# Ethernet_0_V1_01.net
KiCad netlist of a schematic drawn in Altium Designer
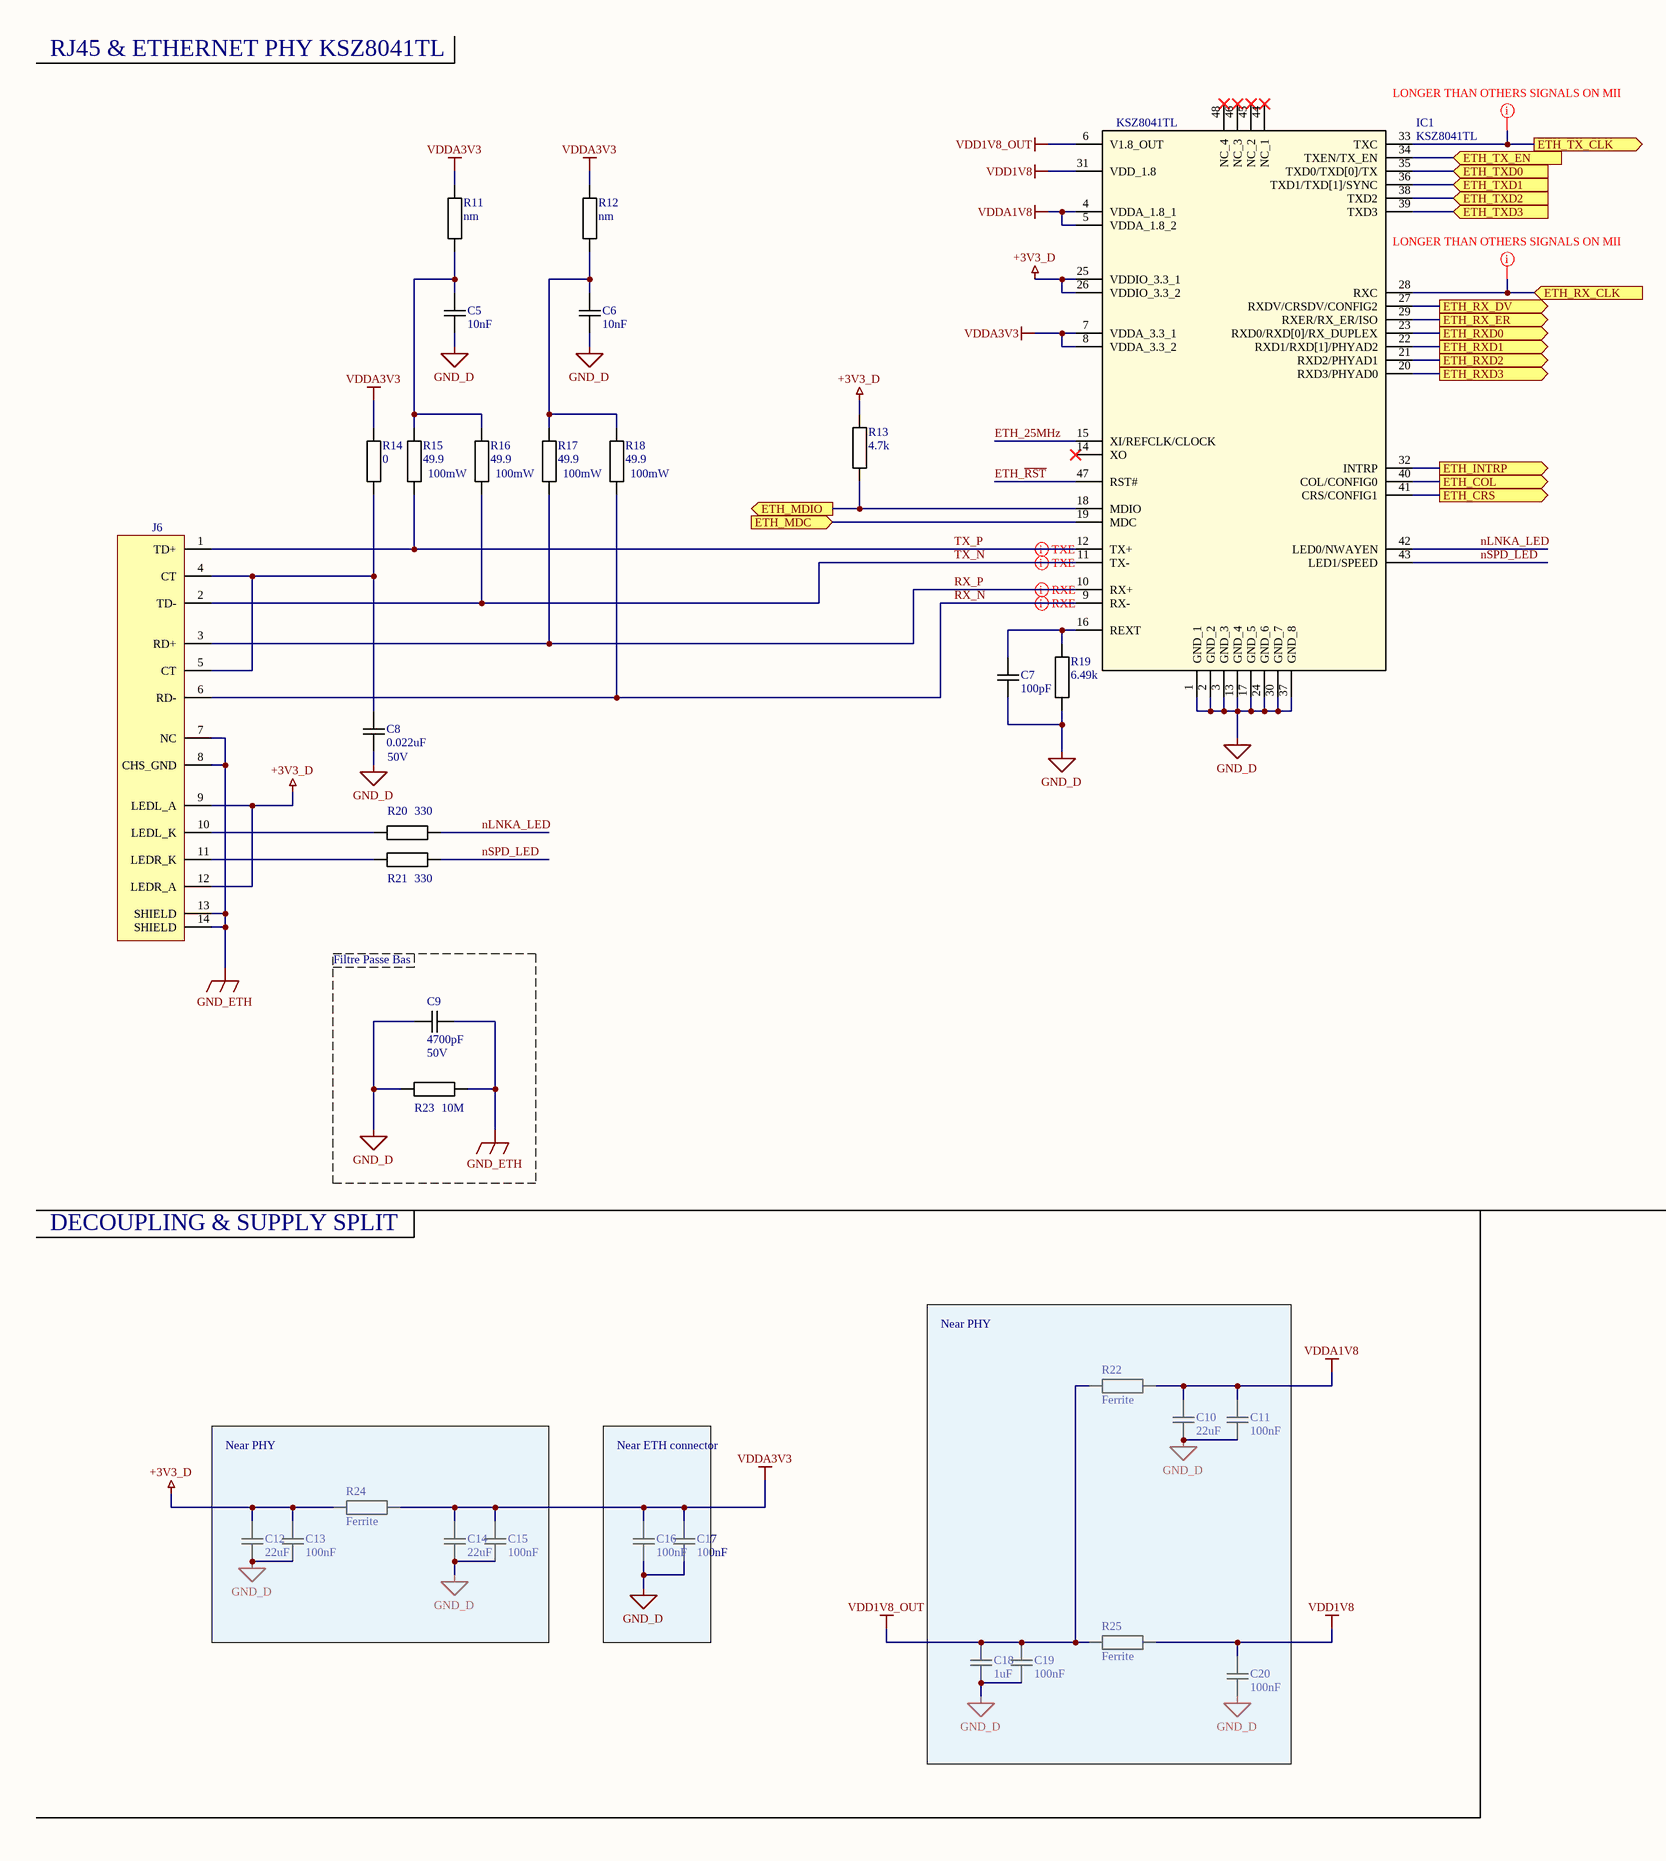
[diagram p0: Ethernet_0_V1_01.SchDoc, left]
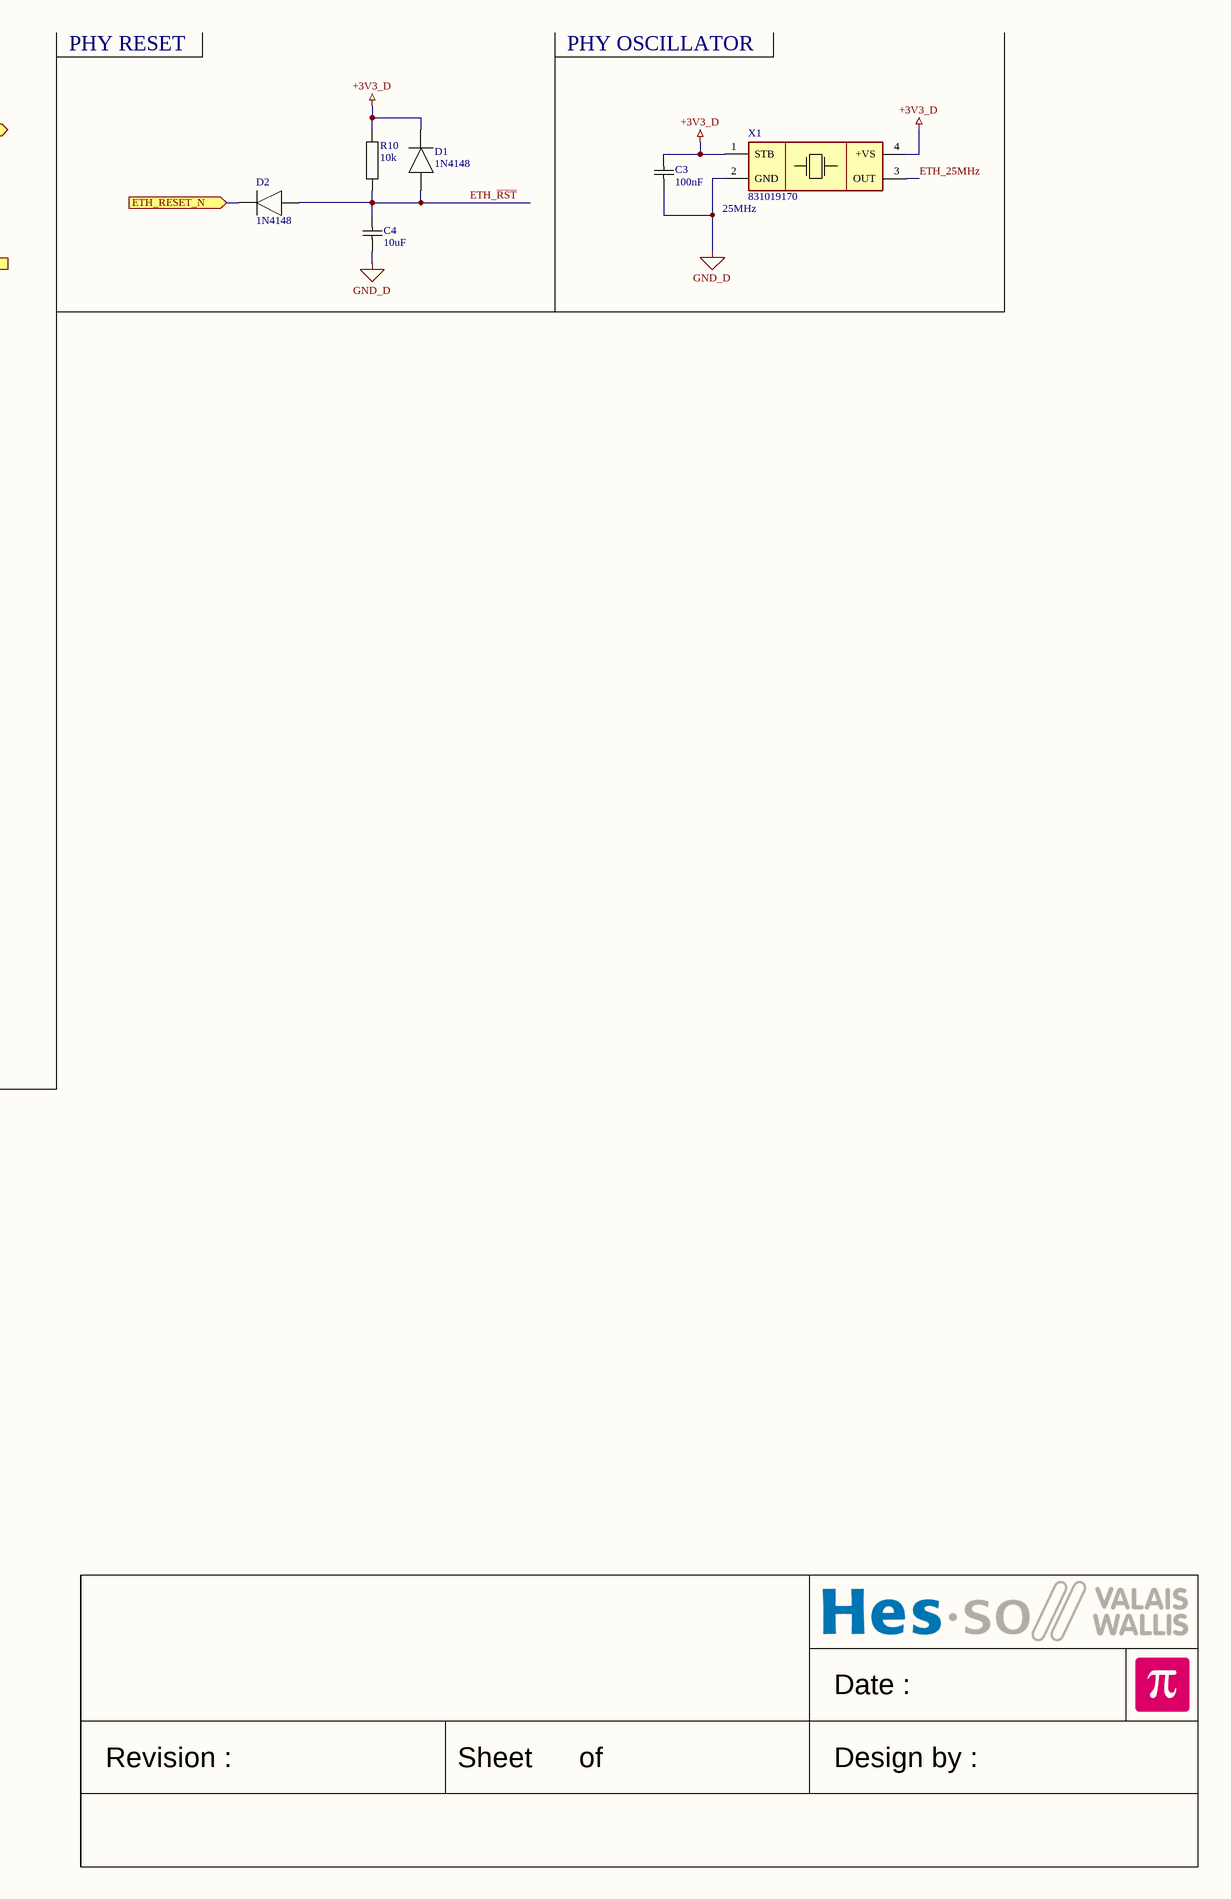
[diagram p1: Ethernet_0_V1_01.SchDoc, right]

(export (version "E")
  (design (tool "Eeschema 10.0.6"))
  (components
    (comp (ref "C3")
      (value "100nF")
      (footprint "CAPACITOR 1608 REFLOW")
      (description "Capacitor X7R 10% 50V 1608(0603)")
      (libsource (lib "Capacitor") (part "Capacitor"))
    )
    (comp (ref "C4")
      (value "10uF")
      (footprint "CAPACITOR 2012 REFLOW")
      (description "Capacitor X7R 10% 50V 1608(0603)")
      (libsource (lib "Capacitor") (part "Capacitor"))
    )
    (comp (ref "C5")
      (value "10nF")
      (footprint "CAPACITOR 1608 REFLOW")
      (description "Capacitor X7R 10% 50V 1608(0603)")
      (libsource (lib "Capacitor") (part "Capacitor"))
    )
    (comp (ref "C6")
      (value "10nF")
      (footprint "CAPACITOR 1608 REFLOW")
      (description "Capacitor X7R 10% 50V 1608(0603)")
      (libsource (lib "Capacitor") (part "Capacitor"))
    )
    (comp (ref "C7")
      (value "100pF")
      (footprint "CAPACITOR 1608 REFLOW")
      (description "Capacitor X7R 10% 50V 1608(0603)")
      (libsource (lib "Capacitor") (part "Capacitor"))
    )
    (comp (ref "C8")
      (value "0.022uF")
      (footprint "CAPACITOR 1608 REFLOW")
      (description "Capacitor")
      (fields (field (name "V") "50V"))
      (libsource (lib "Capacitor") (part "Capacitor"))
    )
    (comp (ref "C9")
      (value "4700pF")
      (footprint "CAPACITOR 1608 REFLOW")
      (description "Capacitor")
      (fields (field (name "U") "50V"))
      (libsource (lib "Capacitor") (part "Capacitor"))
    )
    (comp (ref "C10")
      (value "22uF")
      (footprint "CAPACITOR 2012 REFLOW")
      (description "Capacitor X7R 10% 50V 1608(0603)")
      (libsource (lib "Capacitor") (part "Capacitor"))
    )
    (comp (ref "C11")
      (value "100nF")
      (footprint "CAPACITOR 1608 REFLOW")
      (description "Capacitor X7R 10% 50V 1608(0603)")
      (libsource (lib "Capacitor") (part "Capacitor"))
    )
    (comp (ref "C12")
      (value "22uF")
      (footprint "CAPACITOR 2012 REFLOW")
      (description "Capacitor X7R 10% 50V 1608(0603)")
      (libsource (lib "Capacitor") (part "Capacitor"))
    )
    (comp (ref "C13")
      (value "100nF")
      (footprint "CAPACITOR 1608 REFLOW")
      (description "Capacitor X7R 10% 50V 1608(0603)")
      (libsource (lib "Capacitor") (part "Capacitor"))
    )
    (comp (ref "C14")
      (value "22uF")
      (footprint "CAPACITOR 2012 REFLOW")
      (description "Capacitor X7R 10% 50V 1608(0603)")
      (libsource (lib "Capacitor") (part "Capacitor"))
    )
    (comp (ref "C15")
      (value "100nF")
      (footprint "CAPACITOR 1608 REFLOW")
      (description "Capacitor X7R 10% 50V 1608(0603)")
      (libsource (lib "Capacitor") (part "Capacitor"))
    )
    (comp (ref "C16")
      (value "100nF")
      (footprint "CAPACITOR 1608 REFLOW")
      (description "Capacitor X7R 10% 50V 1608(0603)")
      (libsource (lib "Capacitor") (part "Capacitor"))
    )
    (comp (ref "C17")
      (value "100nF")
      (footprint "CAPACITOR 1608 REFLOW")
      (description "Capacitor X7R 10% 50V 1608(0603)")
      (libsource (lib "Capacitor") (part "Capacitor"))
    )
    (comp (ref "C18")
      (value "1uF")
      (footprint "CAPACITOR 2012 REFLOW")
      (description "Capacitor X7R 10% 50V 1608(0603)")
      (libsource (lib "Capacitor") (part "Capacitor"))
    )
    (comp (ref "C19")
      (value "100nF")
      (footprint "CAPACITOR 1608 REFLOW")
      (description "Capacitor X7R 10% 50V 1608(0603)")
      (libsource (lib "Capacitor") (part "Capacitor"))
    )
    (comp (ref "C20")
      (value "100nF")
      (footprint "CAPACITOR 1608 REFLOW")
      (description "Capacitor X7R 10% 50V 1608(0603)")
      (libsource (lib "Capacitor") (part "Capacitor"))
    )
    (comp (ref "D1")
      (value "1N4148")
      (footprint "DIODE SOD323 REFLOW")
      (description "Diode generic 2 leads")
      (libsource (lib "Diode") (part "DIODE"))
    )
    (comp (ref "D2")
      (value "1N4148")
      (footprint "DIODE SOD323 REFLOW")
      (description "Diode generic 2 leads")
      (libsource (lib "Diode") (part "DIODE"))
    )
    (comp (ref "IC1")
      (value "KSZ8041TL")
      (footprint "SamacSys:QFP50P900X900X105-48N")
      (description "Integrated Circuit")
      (fields
        (field (name "MANUFACTURER_PART_NUMBER") "KSZ8041TL")
        (field (name "MOUSER PART NUMBER") "998-KSZ8041TL")
      )
      (libsource (lib "SamacSys") (part "KSZ8041TL"))
    )
    (comp (ref "J6")
      (value "RJ45-PULSE-J0011D21BNL")
      (footprint "RJ45 PULSE J0011D21BNL")
      (description "Integrated connector modules 10/100 base-TX belMag with LEDs")
      (libsource (lib "Connector") (part "RJ45 PULSE J0011D21BNL"))
    )
    (comp (ref "R10")
      (value "10k")
      (footprint "RESISTOR 1608 REFLOW")
      (description "Resistor 1% 50V 100mW 1608(0603)")
      (libsource (lib "Resistor") (part "Resistor"))
    )
    (comp (ref "R11")
      (value "nm")
      (footprint "RESISTOR 1608 REFLOW")
      (description "Resistor")
      (libsource (lib "Resistor") (part "Resistor"))
    )
    (comp (ref "R12")
      (value "nm")
      (footprint "RESISTOR 1608 REFLOW")
      (description "Resistor")
      (libsource (lib "Resistor") (part "Resistor"))
    )
    (comp (ref "R13")
      (value "4.7k")
      (footprint "RESISTOR 1608 REFLOW")
      (description "Resistor 1% 50V 100mW 1608(0603)")
      (libsource (lib "Resistor") (part "Resistor"))
    )
    (comp (ref "R14")
      (value "0")
      (footprint "RESISTOR 1608 REFLOW")
      (description "Resistor")
      (libsource (lib "Resistor") (part "Resistor"))
    )
    (comp (ref "R15")
      (value "49.9")
      (footprint "RESISTOR 1608 REFLOW")
      (description "Resistor")
      (fields (field (name "W") "100mW"))
      (libsource (lib "Resistor") (part "Resistor"))
    )
    (comp (ref "R16")
      (value "49.9")
      (footprint "RESISTOR 1608 REFLOW")
      (description "Resistor")
      (fields (field (name "W") "100mW"))
      (libsource (lib "Resistor") (part "Resistor"))
    )
    (comp (ref "R17")
      (value "49.9")
      (footprint "RESISTOR 1608 REFLOW")
      (description "Resistor")
      (fields (field (name "W") "100mW"))
      (libsource (lib "Resistor") (part "Resistor"))
    )
    (comp (ref "R18")
      (value "49.9")
      (footprint "RESISTOR 1608 REFLOW")
      (description "Resistor")
      (fields (field (name "W") "100mW"))
      (libsource (lib "Resistor") (part "Resistor"))
    )
    (comp (ref "R19")
      (value "6.49k")
      (footprint "RESISTOR 1608 REFLOW")
      (description "Resistor 1% 50V 100mW 1608(0603)")
      (libsource (lib "Resistor") (part "Resistor"))
    )
    (comp (ref "R20")
      (value "330")
      (footprint "RESISTOR 1608 REFLOW")
      (description "Resistor")
      (libsource (lib "Resistor") (part "Resistor"))
    )
    (comp (ref "R21")
      (value "330")
      (footprint "RESISTOR 1608 REFLOW")
      (description "Resistor")
      (libsource (lib "Resistor") (part "Resistor"))
    )
    (comp (ref "R22")
      (value "Ferrite")
      (footprint "RESISTOR 1608 REFLOW")
      (description "Resistor 1% 50V 100mW 1608(0603)")
      (libsource (lib "Resistor") (part "Resistor"))
    )
    (comp (ref "R23")
      (value "10M")
      (footprint "RESISTOR 1608 REFLOW")
      (description "Resistor")
      (libsource (lib "Resistor") (part "Resistor"))
    )
    (comp (ref "R24")
      (value "Ferrite")
      (footprint "RESISTOR 1608 REFLOW")
      (description "Resistor 1% 50V 100mW 1608(0603)")
      (libsource (lib "Resistor") (part "Resistor"))
    )
    (comp (ref "R25")
      (value "Ferrite")
      (footprint "RESISTOR 1608 REFLOW")
      (description "Resistor 1% 50V 100mW 1608(0603)")
      (libsource (lib "Resistor") (part "Resistor"))
    )
    (comp (ref "X1")
      (value "831019170")
      (footprint "Oscillator C5.2x7.2 IQD LFSPXO")
      (description "Oscillator C5.2x7.2 IQD LFSPXO")
      (fields (field (name "FREQ") "25MHz"))
      (libsource (lib "Oscillator") (part "Oscillator C5.2x7.2 IQD LFSPXO"))
    )
  )
  (nets
    (net (code "1") (name "+3V3_D") (class "Default")
      (node (ref "C12") (pin "2") (pinfunction "2_2") (pintype "passive"))
      (node (ref "C13") (pin "2") (pinfunction "2_2") (pintype "passive"))
      (node (ref "C3") (pin "2") (pinfunction "2_2") (pintype "passive"))
      (node (ref "D1") (pin "1") (pinfunction "C_1") (pintype "passive"))
      (node (ref "IC1") (pin "25") (pinfunction "VDDIO_3.3_1_25") (pintype "passive"))
      (node (ref "IC1") (pin "26") (pinfunction "VDDIO_3.3_2_26") (pintype "passive"))
      (node (ref "J6") (pin "12") (pinfunction "LEDR_A_12") (pintype "passive"))
      (node (ref "J6") (pin "9") (pinfunction "LEDL_A_9") (pintype "passive"))
      (node (ref "R10") (pin "2") (pinfunction "2_2") (pintype "passive"))
      (node (ref "R13") (pin "2") (pinfunction "2_2") (pintype "passive"))
      (node (ref "R24") (pin "2") (pinfunction "2_2") (pintype "passive"))
      (node (ref "X1") (pin "1") (pinfunction "STB_1") (pintype "passive"))
      (node (ref "X1") (pin "4") (pinfunction "+VS_4") (pintype "passive"))
    )
    (net (code "2") (name "/ETH_25MHz") (class "Default")
      (node (ref "IC1") (pin "15") (pinfunction "XI/REFCLK/CLOCK_15") (pintype "passive"))
      (node (ref "X1") (pin "3") (pinfunction "OUT_3") (pintype "passive"))
    )
    (net (code "3") (name "/ETH_COL") (class "Default")
      (node (ref "IC1") (pin "40") (pinfunction "COL/CONFIG0_40") (pintype "passive"))
    )
    (net (code "4") (name "/ETH_CRS") (class "Default")
      (node (ref "IC1") (pin "41") (pinfunction "CRS/CONFIG1_41") (pintype "passive"))
    )
    (net (code "5") (name "/ETH_INTRP") (class "Default")
      (node (ref "IC1") (pin "32") (pinfunction "INTRP_32") (pintype "passive"))
    )
    (net (code "6") (name "/ETH_MDC") (class "Default")
      (node (ref "IC1") (pin "19") (pinfunction "MDC_19") (pintype "passive"))
    )
    (net (code "7") (name "/ETH_MDIO") (class "Default")
      (node (ref "IC1") (pin "18") (pinfunction "MDIO_18") (pintype "passive"))
      (node (ref "R13") (pin "1") (pinfunction "1_1") (pintype "passive"))
    )
    (net (code "8") (name "/ETH_RESET_N") (class "Default")
      (node (ref "D2") (pin "1") (pinfunction "C_1") (pintype "passive"))
    )
    (net (code "9") (name "/ETH_RXD0") (class "Default")
      (node (ref "IC1") (pin "23") (pinfunction "RXD0/RXD[0]/RX_DUPLEX_23") (pintype "passive"))
    )
    (net (code "10") (name "/ETH_RXD1") (class "Default")
      (node (ref "IC1") (pin "22") (pinfunction "RXD1/RXD[1]/PHYAD2_22") (pintype "passive"))
    )
    (net (code "11") (name "/ETH_RXD2") (class "Default")
      (node (ref "IC1") (pin "21") (pinfunction "RXD2/PHYAD1_21") (pintype "passive"))
    )
    (net (code "12") (name "/ETH_RXD3") (class "Default")
      (node (ref "IC1") (pin "20") (pinfunction "RXD3/PHYAD0_20") (pintype "passive"))
    )
    (net (code "13") (name "/ETH_RX_CLK") (class "Default")
      (node (ref "IC1") (pin "28") (pinfunction "RXC_28") (pintype "passive"))
    )
    (net (code "14") (name "/ETH_RX_DV") (class "Default")
      (node (ref "IC1") (pin "27") (pinfunction "RXDV/CRSDV/CONFIG2_27") (pintype "passive"))
    )
    (net (code "15") (name "/ETH_RX_ER") (class "Default")
      (node (ref "IC1") (pin "29") (pinfunction "RXER/RX_ER/ISO_29") (pintype "passive"))
    )
    (net (code "16") (name "/ETH_TXD0") (class "Default")
      (node (ref "IC1") (pin "35") (pinfunction "TXD0/TXD[0]/TX_35") (pintype "passive"))
    )
    (net (code "17") (name "/ETH_TXD1") (class "Default")
      (node (ref "IC1") (pin "36") (pinfunction "TXD1/TXD[1]/SYNC_36") (pintype "passive"))
    )
    (net (code "18") (name "/ETH_TXD2") (class "Default")
      (node (ref "IC1") (pin "38") (pinfunction "TXD2_38") (pintype "passive"))
    )
    (net (code "19") (name "/ETH_TXD3") (class "Default")
      (node (ref "IC1") (pin "39") (pinfunction "TXD3_39") (pintype "passive"))
    )
    (net (code "20") (name "/ETH_TX_CLK") (class "Default")
      (node (ref "IC1") (pin "33") (pinfunction "TXC_33") (pintype "passive"))
    )
    (net (code "21") (name "/ETH_TX_EN") (class "Default")
      (node (ref "IC1") (pin "34") (pinfunction "TXEN/TX_EN_34") (pintype "passive"))
    )
    (net (code "22") (name "/ETH_~{RST}") (class "Default")
      (node (ref "C4") (pin "2") (pinfunction "2_2") (pintype "passive"))
      (node (ref "D1") (pin "2") (pinfunction "A_2") (pintype "passive"))
      (node (ref "D2") (pin "2") (pinfunction "A_2") (pintype "passive"))
      (node (ref "IC1") (pin "47") (pinfunction "RST#_47") (pintype "passive"))
      (node (ref "R10") (pin "1") (pinfunction "1_1") (pintype "passive"))
    )
    (net (code "23") (name "/RX_N") (class "Default")
      (node (ref "IC1") (pin "9") (pinfunction "RX-_9") (pintype "passive"))
      (node (ref "J6") (pin "6") (pinfunction "RD-_6") (pintype "passive"))
      (node (ref "R18") (pin "1") (pinfunction "1_1") (pintype "passive"))
    )
    (net (code "24") (name "/RX_P") (class "Default")
      (node (ref "IC1") (pin "10") (pinfunction "RX+_10") (pintype "passive"))
      (node (ref "J6") (pin "3") (pinfunction "RD+_3") (pintype "passive"))
      (node (ref "R17") (pin "1") (pinfunction "1_1") (pintype "passive"))
    )
    (net (code "25") (name "/TX_N") (class "Default")
      (node (ref "IC1") (pin "11") (pinfunction "TX-_11") (pintype "passive"))
      (node (ref "J6") (pin "2") (pinfunction "TD-_2") (pintype "passive"))
      (node (ref "R16") (pin "1") (pinfunction "1_1") (pintype "passive"))
    )
    (net (code "26") (name "/TX_P") (class "Default")
      (node (ref "IC1") (pin "12") (pinfunction "TX+_12") (pintype "passive"))
      (node (ref "J6") (pin "1") (pinfunction "TD+_1") (pintype "passive"))
      (node (ref "R15") (pin "1") (pinfunction "1_1") (pintype "passive"))
    )
    (net (code "27") (name "/nLNKA_LED") (class "Default")
      (node (ref "IC1") (pin "42") (pinfunction "LED0/NWAYEN_42") (pintype "passive"))
      (node (ref "R20") (pin "1") (pinfunction "1_1") (pintype "passive"))
    )
    (net (code "28") (name "/nSPD_LED") (class "Default")
      (node (ref "IC1") (pin "43") (pinfunction "LED1/SPEED_43") (pintype "passive"))
      (node (ref "R21") (pin "1") (pinfunction "1_1") (pintype "passive"))
    )
    (net (code "29") (name "GND_D") (class "Default")
      (node (ref "C10") (pin "1") (pinfunction "1_1") (pintype "passive"))
      (node (ref "C11") (pin "1") (pinfunction "1_1") (pintype "passive"))
      (node (ref "C12") (pin "1") (pinfunction "1_1") (pintype "passive"))
      (node (ref "C13") (pin "1") (pinfunction "1_1") (pintype "passive"))
      (node (ref "C14") (pin "1") (pinfunction "1_1") (pintype "passive"))
      (node (ref "C15") (pin "1") (pinfunction "1_1") (pintype "passive"))
      (node (ref "C16") (pin "1") (pinfunction "1_1") (pintype "passive"))
      (node (ref "C17") (pin "1") (pinfunction "1_1") (pintype "passive"))
      (node (ref "C18") (pin "1") (pinfunction "1_1") (pintype "passive"))
      (node (ref "C19") (pin "1") (pinfunction "1_1") (pintype "passive"))
      (node (ref "C20") (pin "1") (pinfunction "1_1") (pintype "passive"))
      (node (ref "C3") (pin "1") (pinfunction "1_1") (pintype "passive"))
      (node (ref "C4") (pin "1") (pinfunction "1_1") (pintype "passive"))
      (node (ref "C5") (pin "1") (pinfunction "1_1") (pintype "passive"))
      (node (ref "C6") (pin "1") (pinfunction "1_1") (pintype "passive"))
      (node (ref "C7") (pin "1") (pinfunction "1_1") (pintype "passive"))
      (node (ref "C8") (pin "2") (pinfunction "2_2") (pintype "passive"))
      (node (ref "C9") (pin "1") (pinfunction "1_1") (pintype "passive"))
      (node (ref "IC1") (pin "1") (pinfunction "GND_1_1") (pintype "passive"))
      (node (ref "IC1") (pin "13") (pinfunction "GND_4_13") (pintype "passive"))
      (node (ref "IC1") (pin "17") (pinfunction "GND_5_17") (pintype "passive"))
      (node (ref "IC1") (pin "2") (pinfunction "GND_2_2") (pintype "passive"))
      (node (ref "IC1") (pin "24") (pinfunction "GND_6_24") (pintype "passive"))
      (node (ref "IC1") (pin "3") (pinfunction "GND_3_3") (pintype "passive"))
      (node (ref "IC1") (pin "30") (pinfunction "GND_7_30") (pintype "passive"))
      (node (ref "IC1") (pin "37") (pinfunction "GND_8_37") (pintype "passive"))
      (node (ref "R19") (pin "1") (pinfunction "1_1") (pintype "passive"))
      (node (ref "R23") (pin "2") (pinfunction "2_2") (pintype "passive"))
      (node (ref "X1") (pin "2") (pinfunction "GND_2") (pintype "passive"))
    )
    (net (code "30") (name "GND_ETH") (class "Default")
      (node (ref "C9") (pin "2") (pinfunction "2_2") (pintype "passive"))
      (node (ref "J6") (pin "13") (pinfunction "SHIELD_13") (pintype "passive"))
      (node (ref "J6") (pin "14") (pinfunction "SHIELD_14") (pintype "passive"))
      (node (ref "J6") (pin "7") (pinfunction "NC_7") (pintype "passive"))
      (node (ref "J6") (pin "8") (pinfunction "CHS_GND_8") (pintype "passive"))
      (node (ref "R23") (pin "1") (pinfunction "1_1") (pintype "passive"))
    )
    (net (code "31") (name "Net-(C5-Pad2)") (class "Default")
      (node (ref "C5") (pin "2") (pinfunction "2_2") (pintype "passive"))
      (node (ref "R11") (pin "1") (pinfunction "1_1") (pintype "passive"))
      (node (ref "R15") (pin "2") (pinfunction "2_2") (pintype "passive"))
      (node (ref "R16") (pin "2") (pinfunction "2_2") (pintype "passive"))
    )
    (net (code "32") (name "Net-(C6-Pad2)") (class "Default")
      (node (ref "C6") (pin "2") (pinfunction "2_2") (pintype "passive"))
      (node (ref "R12") (pin "1") (pinfunction "1_1") (pintype "passive"))
      (node (ref "R17") (pin "2") (pinfunction "2_2") (pintype "passive"))
      (node (ref "R18") (pin "2") (pinfunction "2_2") (pintype "passive"))
    )
    (net (code "33") (name "Net-(C8-Pad1)") (class "Default")
      (node (ref "C8") (pin "1") (pinfunction "1_1") (pintype "passive"))
      (node (ref "J6") (pin "4") (pinfunction "CT_4") (pintype "passive"))
      (node (ref "J6") (pin "5") (pinfunction "CT_5") (pintype "passive"))
      (node (ref "R14") (pin "1") (pinfunction "1_1") (pintype "passive"))
    )
    (net (code "34") (name "Net-(IC1-REXT)") (class "Default")
      (node (ref "C7") (pin "2") (pinfunction "2_2") (pintype "passive"))
      (node (ref "IC1") (pin "16") (pinfunction "REXT_16") (pintype "passive"))
      (node (ref "R19") (pin "2") (pinfunction "2_2") (pintype "passive"))
    )
    (net (code "35") (name "Net-(J6-LEDL_K)") (class "Default")
      (node (ref "J6") (pin "10") (pinfunction "LEDL_K_10") (pintype "passive"))
      (node (ref "R20") (pin "2") (pinfunction "2_2") (pintype "passive"))
    )
    (net (code "36") (name "Net-(J6-LEDR_K)") (class "Default")
      (node (ref "J6") (pin "11") (pinfunction "LEDR_K_11") (pintype "passive"))
      (node (ref "R21") (pin "2") (pinfunction "2_2") (pintype "passive"))
    )
    (net (code "37") (name "VDD1V8") (class "Default")
      (node (ref "C20") (pin "2") (pinfunction "2_2") (pintype "passive"))
      (node (ref "IC1") (pin "31") (pinfunction "VDD_1.8_31") (pintype "passive"))
      (node (ref "R25") (pin "1") (pinfunction "1_1") (pintype "passive"))
    )
    (net (code "38") (name "VDD1V8_OUT") (class "Default")
      (node (ref "C18") (pin "2") (pinfunction "2_2") (pintype "passive"))
      (node (ref "C19") (pin "2") (pinfunction "2_2") (pintype "passive"))
      (node (ref "IC1") (pin "6") (pinfunction "V1.8_OUT_6") (pintype "passive"))
      (node (ref "R22") (pin "2") (pinfunction "2_2") (pintype "passive"))
      (node (ref "R25") (pin "2") (pinfunction "2_2") (pintype "passive"))
    )
    (net (code "39") (name "VDDA1V8") (class "Default")
      (node (ref "C10") (pin "2") (pinfunction "2_2") (pintype "passive"))
      (node (ref "C11") (pin "2") (pinfunction "2_2") (pintype "passive"))
      (node (ref "IC1") (pin "4") (pinfunction "VDDA_1.8_1_4") (pintype "passive"))
      (node (ref "IC1") (pin "5") (pinfunction "VDDA_1.8_2_5") (pintype "passive"))
      (node (ref "R22") (pin "1") (pinfunction "1_1") (pintype "passive"))
    )
    (net (code "40") (name "VDDA3V3") (class "Default")
      (node (ref "C14") (pin "2") (pinfunction "2_2") (pintype "passive"))
      (node (ref "C15") (pin "2") (pinfunction "2_2") (pintype "passive"))
      (node (ref "C16") (pin "2") (pinfunction "2_2") (pintype "passive"))
      (node (ref "C17") (pin "2") (pinfunction "2_2") (pintype "passive"))
      (node (ref "IC1") (pin "7") (pinfunction "VDDA_3.3_1_7") (pintype "passive"))
      (node (ref "IC1") (pin "8") (pinfunction "VDDA_3.3_2_8") (pintype "passive"))
      (node (ref "R11") (pin "2") (pinfunction "2_2") (pintype "passive"))
      (node (ref "R12") (pin "2") (pinfunction "2_2") (pintype "passive"))
      (node (ref "R14") (pin "2") (pinfunction "2_2") (pintype "passive"))
      (node (ref "R24") (pin "1") (pinfunction "1_1") (pintype "passive"))
    )
    (net (code "41") (name "unconnected-(IC1-NC_1-Pad44)") (class "Default")
      (node (ref "IC1") (pin "44") (pinfunction "NC_1_44") (pintype "passive+no_connect"))
    )
    (net (code "42") (name "unconnected-(IC1-NC_2-Pad45)") (class "Default")
      (node (ref "IC1") (pin "45") (pinfunction "NC_2_45") (pintype "passive+no_connect"))
    )
    (net (code "43") (name "unconnected-(IC1-NC_3-Pad46)") (class "Default")
      (node (ref "IC1") (pin "46") (pinfunction "NC_3_46") (pintype "passive+no_connect"))
    )
    (net (code "44") (name "unconnected-(IC1-NC_4-Pad48)") (class "Default")
      (node (ref "IC1") (pin "48") (pinfunction "NC_4_48") (pintype "passive+no_connect"))
    )
    (net (code "45") (name "unconnected-(IC1-XO-Pad14)") (class "Default")
      (node (ref "IC1") (pin "14") (pinfunction "XO_14") (pintype "passive+no_connect"))
    )
  )
)
